# esp32.net
KiCad netlist of a schematic drawn in EAGLE
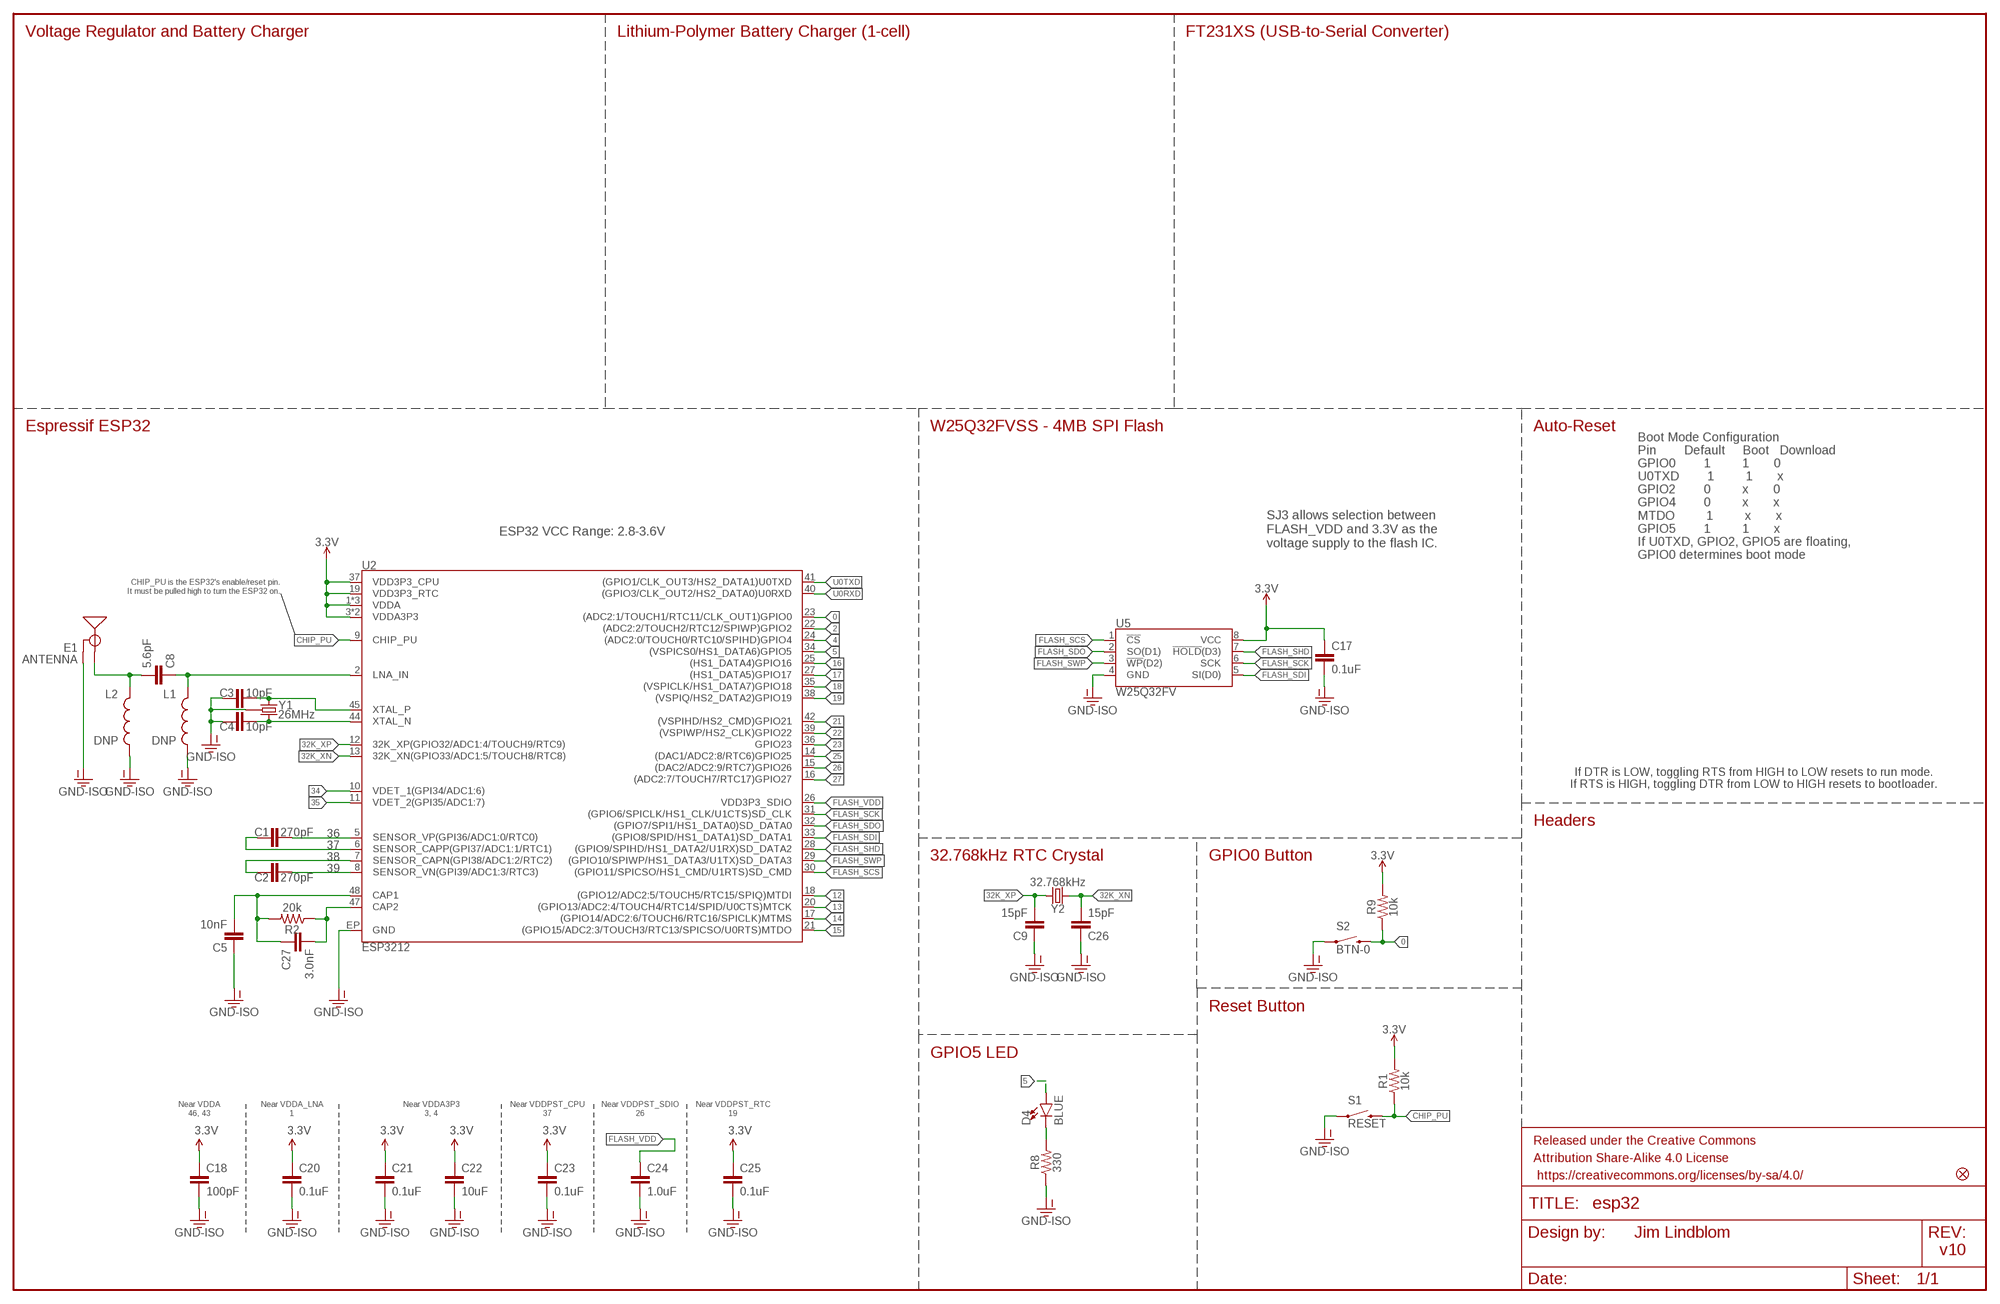
[diagram p0: schematic, sheet 1]

(export (version "E")
  (design (tool "Eeschema 10.0.6"))
  (components
    (comp (ref "C1")
      (value "270pF")
      (footprint "eagle-import:0603")
      (libsource (lib "eagle-import") (part "270PF-50V-5%(0603)"))
    )
    (comp (ref "C2")
      (value "270pF")
      (footprint "eagle-import:0603")
      (libsource (lib "eagle-import") (part "270PF-50V-5%(0603)"))
    )
    (comp (ref "C3")
      (value "10pF")
      (footprint "eagle-import:0603")
      (libsource (lib "eagle-import") (part "10PF-0603-50V-5%"))
    )
    (comp (ref "C4")
      (value "10pF")
      (footprint "eagle-import:0603")
      (libsource (lib "eagle-import") (part "10PF-0603-50V-5%"))
    )
    (comp (ref "C5")
      (value "10nF")
      (footprint "eagle-import:0603")
      (libsource (lib "eagle-import") (part "10NF-0603-50V-10%"))
    )
    (comp (ref "C8")
      (value "5.6pF")
      (footprint "eagle-import:0603")
      (libsource (lib "eagle-import") (part "5.6PF-50V-5%(0603)"))
    )
    (comp (ref "C9")
      (value "15pF")
      (footprint "eagle-import:0603")
      (libsource (lib "eagle-import") (part "15PF-0603-50V-5%"))
    )
    (comp (ref "C17")
      (value "0.1uF")
      (footprint "eagle-import:0603")
      (libsource (lib "eagle-import") (part "0.1UF-0603-25V-(+80/-20%)"))
    )
    (comp (ref "C18")
      (value "100pF")
      (footprint "eagle-import:0603")
      (libsource (lib "eagle-import") (part "100PF-0603-50V-5%"))
    )
    (comp (ref "C20")
      (value "0.1uF")
      (footprint "eagle-import:0603")
      (libsource (lib "eagle-import") (part "0.1UF-0603-25V-(+80/-20%)"))
    )
    (comp (ref "C21")
      (value "0.1uF")
      (footprint "eagle-import:0603")
      (libsource (lib "eagle-import") (part "0.1UF-0603-25V-(+80/-20%)"))
    )
    (comp (ref "C22")
      (value "10uF")
      (footprint "eagle-import:0603")
      (libsource (lib "eagle-import") (part "10UF-0603-6.3V-20%"))
    )
    (comp (ref "C23")
      (value "0.1uF")
      (footprint "eagle-import:0603")
      (libsource (lib "eagle-import") (part "0.1UF-0603-25V-(+80/-20%)"))
    )
    (comp (ref "C24")
      (value "1.0uF")
      (footprint "eagle-import:0603")
      (libsource (lib "eagle-import") (part "1.0UF-0603-16V-10%"))
    )
    (comp (ref "C25")
      (value "0.1uF")
      (footprint "eagle-import:0603")
      (libsource (lib "eagle-import") (part "0.1UF-0603-25V-(+80/-20%)"))
    )
    (comp (ref "C26")
      (value "15pF")
      (footprint "eagle-import:0603")
      (libsource (lib "eagle-import") (part "15PF-0603-50V-5%"))
    )
    (comp (ref "C27")
      (value "3.0nF")
      (footprint "eagle-import:0603")
      (libsource (lib "eagle-import") (part "3.0NF-0603-50V-5%"))
    )
    (comp (ref "D4")
      (value "BLUE")
      (footprint "eagle-import:LED-0603")
      (libsource (lib "eagle-import") (part "LED-BLUE0603"))
    )
    (comp (ref "E1")
      (value "ANTENNA")
      (footprint "eagle-import:TRACE_ANTENNA_2.4GHZ_25.7MM_TUNED")
      (libsource (lib "eagle-import") (part "ANTENNATRACE-TUNED"))
    )
    (comp (ref "FD2")
      (value "FIDUCIALUFIDUCIAL")
      (footprint "eagle-import:MICRO-FIDUCIAL")
      (libsource (lib "eagle-import") (part "FIDUCIALUFIDUCIAL"))
    )
    (comp (ref "FRAME1")
      (value "FRAME-LEDGER")
      (footprint "eagle-import:CREATIVE_COMMONS")
      (libsource (lib "eagle-import") (part "FRAME-LEDGER"))
    )
    (comp (ref "L1")
      (value "DNP")
      (footprint "eagle-import:0603")
      (libsource (lib "eagle-import") (part "INDUCTOR0603"))
    )
    (comp (ref "L2")
      (value "DNP")
      (footprint "eagle-import:0603")
      (libsource (lib "eagle-import") (part "INDUCTOR0603"))
    )
    (comp (ref "R1")
      (value "10k")
      (footprint "eagle-import:0603")
      (libsource (lib "eagle-import") (part "10KOHM-1/10W-1%(0603)0603"))
    )
    (comp (ref "R2")
      (value "20k")
      (footprint "eagle-import:0603")
      (libsource (lib "eagle-import") (part "20KOHM-0603-1/10W-1%"))
    )
    (comp (ref "R8")
      (value "330")
      (footprint "eagle-import:0603")
      (libsource (lib "eagle-import") (part "330OHM1/10W1%(0603)"))
    )
    (comp (ref "R9")
      (value "10k")
      (footprint "eagle-import:0603")
      (libsource (lib "eagle-import") (part "10KOHM-1/10W-1%(0603)0603"))
    )
    (comp (ref "S1")
      (value "RESET")
      (footprint "eagle-import:TACTILE_SWITCH_SMD_4.6X2.8MM")
      (libsource (lib "eagle-import") (part "SWITCH-MOMENTARY-2SMD-4.6X2.8MM"))
    )
    (comp (ref "S2")
      (value "BTN-0")
      (footprint "eagle-import:TACTILE_SWITCH_SMD_4.6X2.8MM")
      (libsource (lib "eagle-import") (part "SWITCH-MOMENTARY-2SMD-4.6X2.8MM"))
    )
    (comp (ref "U2")
      (value "ESP3212")
      (footprint "eagle-import:QFN48-0.4MM")
      (libsource (lib "eagle-import") (part "ESP3212"))
    )
    (comp (ref "U5")
      (value "W25Q32FV")
      (footprint "eagle-import:SOIC-8")
      (libsource (lib "eagle-import") (part "W25Q32FVSS"))
    )
    (comp (ref "Y1")
      (value "26MHz")
      (footprint "eagle-import:CRYSTAL-SMD-3.2X2.5")
      (libsource (lib "eagle-import") (part "CRYSTAL-GROUNDED3.2X2.5"))
    )
    (comp (ref "Y2")
      (value "32.768kHz")
      (footprint "eagle-import:CRYSTAL-SMD-3.2X1.5MM")
      (libsource (lib "eagle-import") (part "CRYSTAL-32.768KHZSMD-3.2X1.5"))
    )
  )
  (nets
    (net (code "1") (name "/36") (class "Default")
      (node (ref "C1") (pin "2") (pinfunction "2_2") (pintype "passive"))
      (node (ref "U2") (pin "5") (pinfunction "SENSOR_VP(GPI36/ADC1:0/RTC0)_5") (pintype "bidirectional"))
    )
    (net (code "2") (name "/37") (class "Default")
      (node (ref "C1") (pin "1") (pinfunction "1_1") (pintype "passive"))
      (node (ref "U2") (pin "6") (pinfunction "SENSOR_CAPP(GPI37/ADC1:1/RTC1)_6") (pintype "bidirectional"))
    )
    (net (code "3") (name "/38") (class "Default")
      (node (ref "C2") (pin "1") (pinfunction "1_1") (pintype "passive"))
      (node (ref "U2") (pin "7") (pinfunction "SENSOR_CAPN(GPI38/ADC1:2/RTC2)_7") (pintype "bidirectional"))
    )
    (net (code "4") (name "/39") (class "Default")
      (node (ref "C2") (pin "2") (pinfunction "2_2") (pintype "passive"))
      (node (ref "U2") (pin "8") (pinfunction "SENSOR_VN(GPI39/ADC1:3/RTC3)_8") (pintype "bidirectional"))
    )
    (net (code "5") (name "0") (class "Default")
      (node (ref "R9") (pin "1") (pinfunction "1_1") (pintype "passive"))
      (node (ref "S2") (pin "3") (pinfunction "2_3") (pintype "passive"))
      (node (ref "S2") (pin "4") (pinfunction "2_4") (pintype "passive"))
      (node (ref "U2") (pin "23") (pinfunction "(ADC2:1/TOUCH1/RTC11/CLK_OUT1)GPIO0_23") (pintype "bidirectional"))
    )
    (net (code "6") (name "2") (class "Default")
      (node (ref "U2") (pin "22") (pinfunction "(ADC2:2/TOUCH2/RTC12/SPIWP)GPIO2_22") (pintype "bidirectional"))
    )
    (net (code "7") (name "3.3V") (class "Default")
      (node (ref "C17") (pin "1") (pinfunction "1_1") (pintype "passive"))
      (node (ref "C18") (pin "1") (pinfunction "1_1") (pintype "passive"))
      (node (ref "C20") (pin "1") (pinfunction "1_1") (pintype "passive"))
      (node (ref "C21") (pin "1") (pinfunction "1_1") (pintype "passive"))
      (node (ref "C22") (pin "1") (pinfunction "1_1") (pintype "passive"))
      (node (ref "C23") (pin "1") (pinfunction "1_1") (pintype "passive"))
      (node (ref "C25") (pin "1") (pinfunction "1_1") (pintype "passive"))
      (node (ref "R1") (pin "2") (pinfunction "2_2") (pintype "passive"))
      (node (ref "R9") (pin "2") (pinfunction "2_2") (pintype "passive"))
      (node (ref "U2") (pin "1") (pinfunction "VDDA_1") (pintype "bidirectional"))
      (node (ref "U2") (pin "19") (pinfunction "VDD3P3_RTC_19") (pintype "bidirectional"))
      (node (ref "U2") (pin "3") (pinfunction "VDDA3P3_3") (pintype "bidirectional"))
      (node (ref "U2") (pin "37") (pinfunction "VDD3P3_CPU_37") (pintype "bidirectional"))
      (node (ref "U2") (pin "4") (pinfunction "VDDA3P3_4") (pintype "bidirectional"))
      (node (ref "U2") (pin "43") (pinfunction "VDDA_43") (pintype "bidirectional"))
      (node (ref "U2") (pin "46") (pinfunction "VDDA_46") (pintype "bidirectional"))
      (node (ref "U5") (pin "8") (pinfunction "VCC_8") (pintype "bidirectional"))
    )
    (net (code "8") (name "4") (class "Default")
      (node (ref "U2") (pin "24") (pinfunction "(ADC2:0/TOUCH0/RTC10/SPIHD)GPIO4_24") (pintype "bidirectional"))
    )
    (net (code "9") (name "5") (class "Default")
      (node (ref "D4") (pin "A") (pinfunction "A_A") (pintype "passive"))
      (node (ref "U2") (pin "34") (pinfunction "(VSPICS0/HS1_DATA6)GPIO5_34") (pintype "bidirectional"))
    )
    (net (code "10") (name "12") (class "Default")
      (node (ref "U2") (pin "18") (pinfunction "(GPIO12/ADC2:5/TOUCH5/RTC15/SPIQ)MTDI_18") (pintype "bidirectional"))
    )
    (net (code "11") (name "13") (class "Default")
      (node (ref "U2") (pin "20") (pinfunction "(GPIO13/ADC2:4/TOUCH4/RTC14/SPID/U0CTS)MTCK_20") (pintype "bidirectional"))
    )
    (net (code "12") (name "14") (class "Default")
      (node (ref "U2") (pin "17") (pinfunction "(GPIO14/ADC2:6/TOUCH6/RTC16/SPICLK)MTMS_17") (pintype "bidirectional"))
    )
    (net (code "13") (name "15") (class "Default")
      (node (ref "U2") (pin "21") (pinfunction "(GPIO15/ADC2:3/TOUCH3/RTC13/SPICSO/U0RTS)MTDO_21") (pintype "bidirectional"))
    )
    (net (code "14") (name "16") (class "Default")
      (node (ref "U2") (pin "25") (pinfunction "(HS1_DATA4)GPIO16_25") (pintype "bidirectional"))
    )
    (net (code "15") (name "17") (class "Default")
      (node (ref "U2") (pin "27") (pinfunction "(HS1_DATA5)GPIO17_27") (pintype "bidirectional"))
    )
    (net (code "16") (name "18") (class "Default")
      (node (ref "U2") (pin "35") (pinfunction "(VSPICLK/HS1_DATA7)GPIO18_35") (pintype "bidirectional"))
    )
    (net (code "17") (name "19") (class "Default")
      (node (ref "U2") (pin "38") (pinfunction "(VSPIQ/HS2_DATA2)GPIO19_38") (pintype "bidirectional"))
    )
    (net (code "18") (name "21") (class "Default")
      (node (ref "U2") (pin "42") (pinfunction "(VSPIHD/HS2_CMD)GPIO21_42") (pintype "bidirectional"))
    )
    (net (code "19") (name "22") (class "Default")
      (node (ref "U2") (pin "39") (pinfunction "(VSPIWP/HS2_CLK)GPIO22_39") (pintype "bidirectional"))
    )
    (net (code "20") (name "23") (class "Default")
      (node (ref "U2") (pin "36") (pinfunction "GPIO23_36") (pintype "bidirectional"))
    )
    (net (code "21") (name "25") (class "Default")
      (node (ref "U2") (pin "14") (pinfunction "(DAC1/ADC2:8/RTC6)GPIO25_14") (pintype "bidirectional"))
    )
    (net (code "22") (name "26") (class "Default")
      (node (ref "U2") (pin "15") (pinfunction "(DAC2/ADC2:9/RTC7)GPIO26_15") (pintype "bidirectional"))
    )
    (net (code "23") (name "27") (class "Default")
      (node (ref "U2") (pin "16") (pinfunction "(ADC2:7/TOUCH7/RTC17)GPIO27_16") (pintype "bidirectional"))
    )
    (net (code "24") (name "32K_XN") (class "Default")
      (node (ref "C26") (pin "2") (pinfunction "2_2") (pintype "passive"))
      (node (ref "U2") (pin "13") (pinfunction "32K_XN(GPIO33/ADC1:5/TOUCH8/RTC8)_13") (pintype "bidirectional"))
      (node (ref "Y2") (pin "P$2") (pinfunction "2_P$2") (pintype "passive"))
    )
    (net (code "25") (name "32K_XP") (class "Default")
      (node (ref "C9") (pin "2") (pinfunction "2_2") (pintype "passive"))
      (node (ref "U2") (pin "12") (pinfunction "32K_XP(GPIO32/ADC1:4/TOUCH9/RTC9)_12") (pintype "bidirectional"))
      (node (ref "Y2") (pin "P$1") (pinfunction "1_P$1") (pintype "passive"))
    )
    (net (code "26") (name "34") (class "Default")
      (node (ref "U2") (pin "10") (pinfunction "VDET_1(GPI34/ADC1:6)_10") (pintype "bidirectional"))
    )
    (net (code "27") (name "35") (class "Default")
      (node (ref "U2") (pin "11") (pinfunction "VDET_2(GPI35/ADC1:7)_11") (pintype "bidirectional"))
    )
    (net (code "28") (name "CHIP_PU") (class "Default")
      (node (ref "R1") (pin "1") (pinfunction "1_1") (pintype "passive"))
      (node (ref "S1") (pin "3") (pinfunction "2_3") (pintype "passive"))
      (node (ref "S1") (pin "4") (pinfunction "2_4") (pintype "passive"))
      (node (ref "U2") (pin "9") (pinfunction "CHIP_PU_9") (pintype "bidirectional"))
    )
    (net (code "29") (name "FLASH_SCK") (class "Default")
      (node (ref "U2") (pin "31") (pinfunction "(GPIO6/SPICLK/HS1_CLK/U1CTS)SD_CLK_31") (pintype "bidirectional"))
      (node (ref "U5") (pin "6") (pinfunction "SCK_6") (pintype "bidirectional"))
    )
    (net (code "30") (name "FLASH_SCS") (class "Default")
      (node (ref "U2") (pin "30") (pinfunction "(GPIO11/SPICSO/HS1_CMD/U1RTS)SD_CMD_30") (pintype "bidirectional"))
      (node (ref "U5") (pin "1") (pinfunction "~{CS}_1") (pintype "bidirectional"))
    )
    (net (code "31") (name "FLASH_SDI") (class "Default")
      (node (ref "U2") (pin "33") (pinfunction "(GPIO8/SPID/HS1_DATA1)SD_DATA1_33") (pintype "bidirectional"))
      (node (ref "U5") (pin "5") (pinfunction "SI(D0)_5") (pintype "bidirectional"))
    )
    (net (code "32") (name "FLASH_SDO") (class "Default")
      (node (ref "U2") (pin "32") (pinfunction "(GPIO7/SPI1/HS1_DATA0)SD_DATA0_32") (pintype "bidirectional"))
      (node (ref "U5") (pin "2") (pinfunction "SO(D1)_2") (pintype "bidirectional"))
    )
    (net (code "33") (name "FLASH_SHD") (class "Default")
      (node (ref "U2") (pin "28") (pinfunction "(GPIO9/SPIHD/HS1_DATA2/U1RX)SD_DATA2_28") (pintype "bidirectional"))
      (node (ref "U5") (pin "7") (pinfunction "~{HOLD}(D3)_7") (pintype "bidirectional"))
    )
    (net (code "34") (name "FLASH_SWP") (class "Default")
      (node (ref "U2") (pin "29") (pinfunction "(GPIO10/SPIWP/HS1_DATA3/U1TX)SD_DATA3_29") (pintype "bidirectional"))
      (node (ref "U5") (pin "3") (pinfunction "~{WP}(D2)_3") (pintype "bidirectional"))
    )
    (net (code "35") (name "FLASH_VDD") (class "Default")
      (node (ref "C24") (pin "1") (pinfunction "1_1") (pintype "passive"))
      (node (ref "U2") (pin "26") (pinfunction "VDD3P3_SDIO_26") (pintype "bidirectional"))
    )
    (net (code "36") (name "GND-ISO") (class "Default")
      (node (ref "C17") (pin "2") (pinfunction "2_2") (pintype "passive"))
      (node (ref "C18") (pin "2") (pinfunction "2_2") (pintype "passive"))
      (node (ref "C20") (pin "2") (pinfunction "2_2") (pintype "passive"))
      (node (ref "C21") (pin "2") (pinfunction "2_2") (pintype "passive"))
      (node (ref "C22") (pin "2") (pinfunction "2_2") (pintype "passive"))
      (node (ref "C23") (pin "2") (pinfunction "2_2") (pintype "passive"))
      (node (ref "C24") (pin "2") (pinfunction "2_2") (pintype "passive"))
      (node (ref "C25") (pin "2") (pinfunction "2_2") (pintype "passive"))
      (node (ref "C26") (pin "1") (pinfunction "1_1") (pintype "passive"))
      (node (ref "C3") (pin "1") (pinfunction "1_1") (pintype "passive"))
      (node (ref "C4") (pin "1") (pinfunction "1_1") (pintype "passive"))
      (node (ref "C5") (pin "1") (pinfunction "1_1") (pintype "passive"))
      (node (ref "C9") (pin "1") (pinfunction "1_1") (pintype "passive"))
      (node (ref "E1") (pin "GND") (pinfunction "GND_GND") (pintype "bidirectional"))
      (node (ref "E1") (pin "GND2") (pinfunction "GND_GND2") (pintype "bidirectional"))
      (node (ref "L1") (pin "2") (pinfunction "2_2") (pintype "passive"))
      (node (ref "L2") (pin "2") (pinfunction "2_2") (pintype "passive"))
      (node (ref "R8") (pin "1") (pinfunction "1_1") (pintype "passive"))
      (node (ref "S1") (pin "1") (pinfunction "1_1") (pintype "passive"))
      (node (ref "S1") (pin "2") (pinfunction "1_2") (pintype "passive"))
      (node (ref "S2") (pin "1") (pinfunction "1_1") (pintype "passive"))
      (node (ref "S2") (pin "2") (pinfunction "1_2") (pintype "passive"))
      (node (ref "U2") (pin "EP") (pinfunction "GND_EP") (pintype "bidirectional"))
      (node (ref "U5") (pin "4") (pinfunction "GND_4") (pintype "bidirectional"))
      (node (ref "Y1") (pin "2") (pinfunction "GND_2") (pintype "passive"))
      (node (ref "Y1") (pin "4") (pinfunction "GND_4") (pintype "passive"))
    )
    (net (code "37") (name "Net-(D4-PadC)") (class "Default")
      (node (ref "D4") (pin "C") (pinfunction "C_C") (pintype "passive"))
      (node (ref "R8") (pin "2") (pinfunction "2_2") (pintype "passive"))
    )
    (net (code "38") (name "Net-(E1-SIGNAL)") (class "Default")
      (node (ref "C8") (pin "2") (pinfunction "2_2") (pintype "passive"))
      (node (ref "E1") (pin "ANT") (pinfunction "SIGNAL_ANT") (pintype "bidirectional"))
      (node (ref "L2") (pin "1") (pinfunction "1_1") (pintype "passive"))
    )
    (net (code "39") (name "Net-(U2-CAP1)") (class "Default")
      (node (ref "C27") (pin "1") (pinfunction "1_1") (pintype "passive"))
      (node (ref "C5") (pin "2") (pinfunction "2_2") (pintype "passive"))
      (node (ref "R2") (pin "2") (pinfunction "2_2") (pintype "passive"))
      (node (ref "U2") (pin "48") (pinfunction "CAP1_48") (pintype "bidirectional"))
    )
    (net (code "40") (name "Net-(U2-CAP2)") (class "Default")
      (node (ref "C27") (pin "2") (pinfunction "2_2") (pintype "passive"))
      (node (ref "R2") (pin "1") (pinfunction "1_1") (pintype "passive"))
      (node (ref "U2") (pin "47") (pinfunction "CAP2_47") (pintype "bidirectional"))
    )
    (net (code "41") (name "Net-(U2-LNA_IN)") (class "Default")
      (node (ref "C8") (pin "1") (pinfunction "1_1") (pintype "passive"))
      (node (ref "L1") (pin "1") (pinfunction "1_1") (pintype "passive"))
      (node (ref "U2") (pin "2") (pinfunction "LNA_IN_2") (pintype "bidirectional"))
    )
    (net (code "42") (name "Net-(U2-XTAL_N)") (class "Default")
      (node (ref "C4") (pin "2") (pinfunction "2_2") (pintype "passive"))
      (node (ref "U2") (pin "44") (pinfunction "XTAL_N_44") (pintype "bidirectional"))
      (node (ref "Y1") (pin "3") (pinfunction "2_3") (pintype "passive"))
    )
    (net (code "43") (name "Net-(U2-XTAL_P)") (class "Default")
      (node (ref "C3") (pin "2") (pinfunction "2_2") (pintype "passive"))
      (node (ref "U2") (pin "45") (pinfunction "XTAL_P_45") (pintype "bidirectional"))
      (node (ref "Y1") (pin "1") (pinfunction "1_1") (pintype "passive"))
    )
    (net (code "44") (name "U0RXD") (class "Default")
      (node (ref "U2") (pin "40") (pinfunction "(GPIO3/CLK_OUT2/HS2_DATA0)U0RXD_40") (pintype "bidirectional"))
    )
    (net (code "45") (name "U0TXD") (class "Default")
      (node (ref "U2") (pin "41") (pinfunction "(GPIO1/CLK_OUT3/HS2_DATA1)U0TXD_41") (pintype "bidirectional"))
    )
  )
)
